# Doggy.net
KiCad netlist of a schematic drawn in Altium Designer
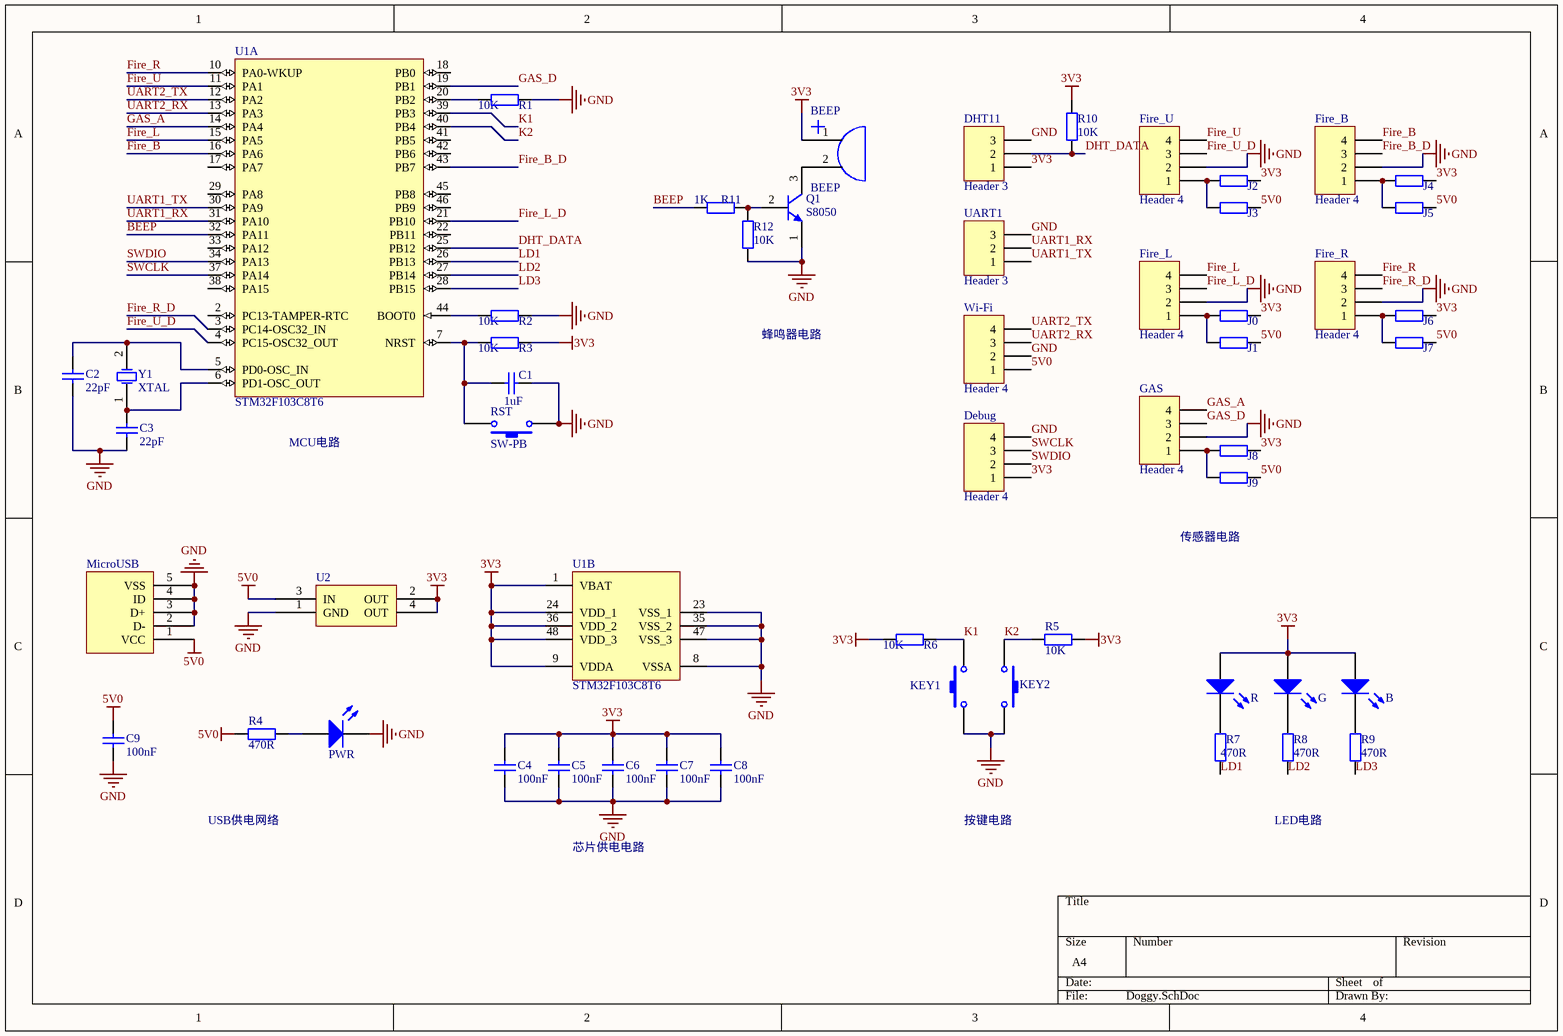
[diagram p0: Doggy.SchDoc]

(export (version "E")
  (design (tool "Eeschema 10.0.6"))
  (components
    (comp (ref "B")
      (value "LED0")
      (footprint "LED_0805")
      (description "发光二极管")
      (fields (field (name "PUBLISHER") "Altium Limited"))
      (libsource (lib "Fszhang") (part "LED0"))
    )
    (comp (ref "BEEP")
      (value "BEEP")
      (footprint "Beep")
      (description "蜂鸣器")
      (libsource (lib "Fszhang") (part "BEEP"))
    )
    (comp (ref "C1")
      (value "1uF")
      (footprint "C-RAD-0805")
      (description "无极性电容")
      (fields (field (name "Comment") "Cap") (field (name "PUBLISHER") "Altium Limited"))
      (libsource (lib "Fszhang") (part "Cap"))
    )
    (comp (ref "C2")
      (value "22pF")
      (footprint "C-RAD-0805")
      (description "无极性电容")
      (fields (field (name "Comment") "Cap") (field (name "PUBLISHER") "Altium Limited"))
      (libsource (lib "Fszhang") (part "Cap"))
    )
    (comp (ref "C3")
      (value "22pF")
      (footprint "C-RAD-0805")
      (description "无极性电容")
      (fields (field (name "Comment") "Cap") (field (name "PUBLISHER") "Altium Limited"))
      (libsource (lib "Fszhang") (part "Cap"))
    )
    (comp (ref "C4")
      (value "100nF")
      (footprint "C-RAD-0805")
      (description "无极性电容")
      (fields (field (name "Comment") "Cap") (field (name "PUBLISHER") "Altium Limited"))
      (libsource (lib "Fszhang") (part "Cap"))
    )
    (comp (ref "C5")
      (value "100nF")
      (footprint "C-RAD-0805")
      (description "无极性电容")
      (fields (field (name "Comment") "Cap") (field (name "PUBLISHER") "Altium Limited"))
      (libsource (lib "Fszhang") (part "Cap"))
    )
    (comp (ref "C6")
      (value "100nF")
      (footprint "C-RAD-0805")
      (description "无极性电容")
      (fields (field (name "Comment") "Cap") (field (name "PUBLISHER") "Altium Limited"))
      (libsource (lib "Fszhang") (part "Cap"))
    )
    (comp (ref "C7")
      (value "100nF")
      (footprint "C-RAD-0805")
      (description "无极性电容")
      (fields (field (name "Comment") "Cap") (field (name "PUBLISHER") "Altium Limited"))
      (libsource (lib "Fszhang") (part "Cap"))
    )
    (comp (ref "C8")
      (value "100nF")
      (footprint "C-RAD-0805")
      (description "无极性电容")
      (fields (field (name "Comment") "Cap") (field (name "PUBLISHER") "Altium Limited"))
      (libsource (lib "Fszhang") (part "Cap"))
    )
    (comp (ref "C9")
      (value "100nF")
      (footprint "C-RAD-0805")
      (description "无极性电容")
      (fields (field (name "Comment") "Cap") (field (name "PUBLISHER") "Altium Limited"))
      (libsource (lib "Fszhang") (part "Cap"))
    )
    (comp (ref "Debug")
      (value "Header 4")
      (footprint "HDR1X4")
      (description "Header, 4-Pin")
      (fields (field (name "PUBLISHER") "Altium Limited"))
      (libsource (lib "Miscellaneous Connectors") (part "Header 4"))
    )
    (comp (ref "DHT11")
      (value "Header 3")
      (footprint "HDR1X3")
      (description "Header, 3-Pin")
      (fields (field (name "PUBLISHER") "Altium Limited"))
      (libsource (lib "Miscellaneous Connectors") (part "Header 3"))
    )
    (comp (ref "Fire_B")
      (value "Header 4")
      (footprint "HDR1X4")
      (description "Header, 4-Pin")
      (fields (field (name "PUBLISHER") "Altium Limited"))
      (libsource (lib "Miscellaneous Connectors") (part "Header 4"))
    )
    (comp (ref "Fire_L")
      (value "Header 4")
      (footprint "HDR1X4")
      (description "Header, 4-Pin")
      (fields (field (name "PUBLISHER") "Altium Limited"))
      (libsource (lib "Miscellaneous Connectors") (part "Header 4"))
    )
    (comp (ref "Fire_R")
      (value "Header 4")
      (footprint "HDR1X4")
      (description "Header, 4-Pin")
      (fields (field (name "PUBLISHER") "Altium Limited"))
      (libsource (lib "Miscellaneous Connectors") (part "Header 4"))
    )
    (comp (ref "Fire_U")
      (value "Header 4")
      (footprint "HDR1X4")
      (description "Header, 4-Pin")
      (fields (field (name "PUBLISHER") "Altium Limited"))
      (libsource (lib "Miscellaneous Connectors") (part "Header 4"))
    )
    (comp (ref "G")
      (value "LED0")
      (footprint "LED_0805")
      (description "发光二极管")
      (fields (field (name "PUBLISHER") "Altium Limited"))
      (libsource (lib "Fszhang") (part "LED0"))
    )
    (comp (ref "GAS")
      (value "Header 4")
      (footprint "HDR1X4")
      (description "Header, 4-Pin")
      (fields (field (name "PUBLISHER") "Altium Limited"))
      (libsource (lib "Miscellaneous Connectors") (part "Header 4"))
    )
    (comp (ref "J0")
      (value "Res1")
      (footprint "0805-1")
      (description "贴片电阻")
      (fields (field (name "PUBLISHER") "Altium Limited"))
      (libsource (lib "Fszhang") (part "Res1"))
    )
    (comp (ref "J1")
      (value "Res1")
      (footprint "0805-1")
      (description "贴片电阻")
      (fields (field (name "PUBLISHER") "Altium Limited"))
      (libsource (lib "Fszhang") (part "Res1"))
    )
    (comp (ref "J2")
      (value "Res1")
      (footprint "0805-1")
      (description "贴片电阻")
      (fields (field (name "PUBLISHER") "Altium Limited"))
      (libsource (lib "Fszhang") (part "Res1"))
    )
    (comp (ref "J3")
      (value "Res1")
      (footprint "0805-1")
      (description "贴片电阻")
      (fields (field (name "PUBLISHER") "Altium Limited"))
      (libsource (lib "Fszhang") (part "Res1"))
    )
    (comp (ref "J4")
      (value "Res1")
      (footprint "0805-1")
      (description "贴片电阻")
      (fields (field (name "PUBLISHER") "Altium Limited"))
      (libsource (lib "Fszhang") (part "Res1"))
    )
    (comp (ref "J5")
      (value "Res1")
      (footprint "0805-1")
      (description "贴片电阻")
      (fields (field (name "PUBLISHER") "Altium Limited"))
      (libsource (lib "Fszhang") (part "Res1"))
    )
    (comp (ref "J6")
      (value "Res1")
      (footprint "0805-1")
      (description "贴片电阻")
      (fields (field (name "PUBLISHER") "Altium Limited"))
      (libsource (lib "Fszhang") (part "Res1"))
    )
    (comp (ref "J7")
      (value "Res1")
      (footprint "0805-1")
      (description "贴片电阻")
      (fields (field (name "PUBLISHER") "Altium Limited"))
      (libsource (lib "Fszhang") (part "Res1"))
    )
    (comp (ref "J8")
      (value "Res1")
      (footprint "0805-1")
      (description "贴片电阻")
      (fields (field (name "PUBLISHER") "Altium Limited"))
      (libsource (lib "Fszhang") (part "Res1"))
    )
    (comp (ref "J9")
      (value "Res1")
      (footprint "0805-1")
      (description "贴片电阻")
      (fields (field (name "PUBLISHER") "Altium Limited"))
      (libsource (lib "Fszhang") (part "Res1"))
    )
    (comp (ref "KEY1")
      (value "SW-PB")
      (footprint "SW_PB2_A1")
      (description "微动开关")
      (fields (field (name "PUBLISHER") "Altium Limited"))
      (libsource (lib "Fszhang") (part "SW-PB"))
    )
    (comp (ref "KEY2")
      (value "SW-PB")
      (footprint "SW_PB2_A1")
      (description "微动开关")
      (fields (field (name "PUBLISHER") "Altium Limited"))
      (libsource (lib "Fszhang") (part "SW-PB"))
    )
    (comp (ref "MicroUSB")
      (value "USB_M")
      (footprint "USB_MICRO")
      (description "MicroUSB接口")
      (libsource (lib "Fszhang") (part "USB_M"))
    )
    (comp (ref "PWR")
      (value "LED0")
      (footprint "LED_0805")
      (description "发光二极管")
      (fields (field (name "PUBLISHER") "Altium Limited"))
      (libsource (lib "Fszhang") (part "LED0"))
    )
    (comp (ref "Q1")
      (value "S8050")
      (footprint "TO-92A")
      (description "NPN三极管")
      (fields (field (name "PUBLISHER") "Altium Limited"))
      (libsource (lib "Fszhang") (part "S8050"))
    )
    (comp (ref "R")
      (value "LED0")
      (footprint "LED_0805")
      (description "发光二极管")
      (fields (field (name "PUBLISHER") "Altium Limited"))
      (libsource (lib "Fszhang") (part "LED0"))
    )
    (comp (ref "R1")
      (value "10K")
      (footprint "0805-1")
      (description "贴片电阻")
      (fields (field (name "Comment") "Res1") (field (name "PUBLISHER") "Altium Limited"))
      (libsource (lib "Fszhang") (part "Res1"))
    )
    (comp (ref "R2")
      (value "10K")
      (footprint "0805-1")
      (description "贴片电阻")
      (fields (field (name "Comment") "Res1") (field (name "PUBLISHER") "Altium Limited"))
      (libsource (lib "Fszhang") (part "Res1"))
    )
    (comp (ref "R3")
      (value "10K")
      (footprint "0805-1")
      (description "贴片电阻")
      (fields (field (name "Comment") "Res1") (field (name "PUBLISHER") "Altium Limited"))
      (libsource (lib "Fszhang") (part "Res1"))
    )
    (comp (ref "R4")
      (value "470R")
      (footprint "0805-1")
      (description "贴片电阻")
      (fields (field (name "Comment") "Res1") (field (name "PUBLISHER") "Altium Limited"))
      (libsource (lib "Fszhang") (part "Res1"))
    )
    (comp (ref "R5")
      (value "10K")
      (footprint "0805-1")
      (description "贴片电阻")
      (fields (field (name "Comment") "Res1") (field (name "PUBLISHER") "Altium Limited"))
      (libsource (lib "") (part "Res1_1"))
    )
    (comp (ref "R6")
      (value "10K")
      (footprint "0805-1")
      (description "贴片电阻")
      (fields (field (name "Comment") "Res1") (field (name "PUBLISHER") "Altium Limited"))
      (libsource (lib "Fszhang") (part "Res1"))
    )
    (comp (ref "R7")
      (value "470R")
      (footprint "0805-1")
      (description "贴片电阻")
      (fields (field (name "Comment") "Res1") (field (name "PUBLISHER") "Altium Limited"))
      (libsource (lib "") (part "Res1_2"))
    )
    (comp (ref "R8")
      (value "470R")
      (footprint "0805-1")
      (description "贴片电阻")
      (fields (field (name "Comment") "Res1") (field (name "PUBLISHER") "Altium Limited"))
      (libsource (lib "") (part "Res1_2"))
    )
    (comp (ref "R9")
      (value "470R")
      (footprint "0805-1")
      (description "贴片电阻")
      (fields (field (name "Comment") "Res1") (field (name "PUBLISHER") "Altium Limited"))
      (libsource (lib "") (part "Res1_2"))
    )
    (comp (ref "R10")
      (value "10K")
      (footprint "0805-1")
      (description "贴片电阻")
      (fields (field (name "Comment") "Res1") (field (name "PUBLISHER") "Altium Limited"))
      (libsource (lib "") (part "Res1_2"))
    )
    (comp (ref "R11")
      (value "1K")
      (footprint "0805-1")
      (description "贴片电阻")
      (fields (field (name "Comment") "Res1") (field (name "PUBLISHER") "Altium Limited"))
      (libsource (lib "Fszhang") (part "Res1"))
    )
    (comp (ref "R12")
      (value "10K")
      (footprint "0805-1")
      (description "贴片电阻")
      (fields (field (name "Comment") "Res1") (field (name "PUBLISHER") "Altium Limited"))
      (libsource (lib "") (part "Res1_2"))
    )
    (comp (ref "RST")
      (value "SW-PB")
      (footprint "SW_PB2_A1")
      (description "微动开关")
      (fields (field (name "PUBLISHER") "Altium Limited"))
      (libsource (lib "Fszhang") (part "SW-PB"))
    )
    (comp (ref "U1")
      (value "STM32F103C8T6")
      (footprint "STM-LQFP48_N")
      (libsource (lib "STMicroelectronics STM32 F1") (part "STM32F103C8T6"))
    )
    (comp (ref "U2")
      (value "AMS1117-3.3")
      (footprint "SOT-223")
      (description "3.3V稳压芯片")
      (libsource (lib "Fszhang") (part "ASM1117"))
    )
    (comp (ref "UART1")
      (value "Header 3")
      (footprint "HDR1X3")
      (description "Header, 3-Pin")
      (fields (field (name "PUBLISHER") "Altium Limited"))
      (libsource (lib "Miscellaneous Connectors") (part "Header 3"))
    )
    (comp (ref "Wi-Fi")
      (value "Header 4")
      (footprint "HDR1X4")
      (description "Header, 4-Pin")
      (fields (field (name "PUBLISHER") "Altium Limited"))
      (libsource (lib "Miscellaneous Connectors") (part "Header 4"))
    )
    (comp (ref "Y1")
      (value "XTAL")
      (footprint "X-HC49U")
      (description "Crystal Oscillator")
      (fields (field (name "PUBLISHER") "Altium Limited"))
      (libsource (lib "Miscellaneous Devices") (part "XTAL"))
    )
  )
  (nets
    (net (code "1") (name "/BEEP") (class "Default")
      (node (ref "R11") (pin "1") (pinfunction "1_1") (pintype "passive"))
      (node (ref "U1") (pin "32") (pinfunction "PA11_32") (pintype "bidirectional"))
    )
    (net (code "2") (name "/DHT_DATA") (class "Default")
      (node (ref "DHT11") (pin "2") (pinfunction "2_2") (pintype "passive"))
      (node (ref "R10") (pin "1") (pinfunction "1_1") (pintype "passive"))
      (node (ref "U1") (pin "25") (pinfunction "PB12_25") (pintype "bidirectional"))
    )
    (net (code "3") (name "/Fire_B") (class "Default")
      (node (ref "Fire_B") (pin "4") (pinfunction "4_4") (pintype "passive"))
      (node (ref "U1") (pin "16") (pinfunction "PA6_16") (pintype "bidirectional"))
    )
    (net (code "4") (name "/Fire_B_D") (class "Default")
      (node (ref "Fire_B") (pin "3") (pinfunction "3_3") (pintype "passive"))
      (node (ref "U1") (pin "43") (pinfunction "PB7_43") (pintype "bidirectional"))
    )
    (net (code "5") (name "/Fire_L") (class "Default")
      (node (ref "Fire_L") (pin "4") (pinfunction "4_4") (pintype "passive"))
      (node (ref "U1") (pin "15") (pinfunction "PA5_15") (pintype "bidirectional"))
    )
    (net (code "6") (name "/Fire_L_D") (class "Default")
      (node (ref "Fire_L") (pin "3") (pinfunction "3_3") (pintype "passive"))
      (node (ref "U1") (pin "21") (pinfunction "PB10_21") (pintype "bidirectional"))
    )
    (net (code "7") (name "/Fire_R") (class "Default")
      (node (ref "Fire_R") (pin "4") (pinfunction "4_4") (pintype "passive"))
      (node (ref "U1") (pin "10") (pinfunction "PA0-WKUP_10") (pintype "bidirectional"))
    )
    (net (code "8") (name "/Fire_R_D") (class "Default")
      (node (ref "Fire_R") (pin "3") (pinfunction "3_3") (pintype "passive"))
      (node (ref "U1") (pin "3") (pinfunction "PC14-OSC32_IN_3") (pintype "bidirectional"))
    )
    (net (code "9") (name "/Fire_U") (class "Default")
      (node (ref "Fire_U") (pin "4") (pinfunction "4_4") (pintype "passive"))
      (node (ref "U1") (pin "11") (pinfunction "PA1_11") (pintype "bidirectional"))
    )
    (net (code "10") (name "/Fire_U_D") (class "Default")
      (node (ref "Fire_U") (pin "3") (pinfunction "3_3") (pintype "passive"))
      (node (ref "U1") (pin "4") (pinfunction "PC15-OSC32_OUT_4") (pintype "bidirectional"))
    )
    (net (code "11") (name "/GAS_A") (class "Default")
      (node (ref "GAS") (pin "4") (pinfunction "4_4") (pintype "passive"))
      (node (ref "U1") (pin "14") (pinfunction "PA4_14") (pintype "bidirectional"))
    )
    (net (code "12") (name "/GAS_D") (class "Default")
      (node (ref "GAS") (pin "3") (pinfunction "3_3") (pintype "passive"))
      (node (ref "U1") (pin "19") (pinfunction "PB1_19") (pintype "bidirectional"))
    )
    (net (code "13") (name "/K1") (class "Default")
      (node (ref "KEY1") (pin "2") (pinfunction "2_2") (pintype "passive"))
      (node (ref "R6") (pin "2") (pinfunction "2_2") (pintype "passive"))
      (node (ref "U1") (pin "39") (pinfunction "PB3_39") (pintype "bidirectional"))
    )
    (net (code "14") (name "/K2") (class "Default")
      (node (ref "KEY2") (pin "1") (pinfunction "1_1") (pintype "passive"))
      (node (ref "R5") (pin "2") (pinfunction "2_2") (pintype "passive"))
      (node (ref "U1") (pin "40") (pinfunction "PB4_40") (pintype "bidirectional"))
    )
    (net (code "15") (name "/LD1") (class "Default")
      (node (ref "R7") (pin "1") (pinfunction "1_1") (pintype "passive"))
      (node (ref "U1") (pin "26") (pinfunction "PB13_26") (pintype "bidirectional"))
    )
    (net (code "16") (name "/LD2") (class "Default")
      (node (ref "R8") (pin "1") (pinfunction "1_1") (pintype "passive"))
      (node (ref "U1") (pin "27") (pinfunction "PB14_27") (pintype "bidirectional"))
    )
    (net (code "17") (name "/LD3") (class "Default")
      (node (ref "R9") (pin "1") (pinfunction "1_1") (pintype "passive"))
      (node (ref "U1") (pin "28") (pinfunction "PB15_28") (pintype "bidirectional"))
    )
    (net (code "18") (name "/SWCLK") (class "Default")
      (node (ref "Debug") (pin "3") (pinfunction "3_3") (pintype "passive"))
      (node (ref "U1") (pin "37") (pinfunction "PA14_37") (pintype "bidirectional"))
    )
    (net (code "19") (name "/SWDIO") (class "Default")
      (node (ref "Debug") (pin "2") (pinfunction "2_2") (pintype "passive"))
      (node (ref "U1") (pin "34") (pinfunction "PA13_34") (pintype "bidirectional"))
    )
    (net (code "20") (name "/UART1_RX") (class "Default")
      (node (ref "U1") (pin "31") (pinfunction "PA10_31") (pintype "bidirectional"))
      (node (ref "UART1") (pin "2") (pinfunction "2_2") (pintype "passive"))
    )
    (net (code "21") (name "/UART1_TX") (class "Default")
      (node (ref "U1") (pin "30") (pinfunction "PA9_30") (pintype "bidirectional"))
      (node (ref "UART1") (pin "1") (pinfunction "1_1") (pintype "passive"))
    )
    (net (code "22") (name "/UART2_RX") (class "Default")
      (node (ref "U1") (pin "13") (pinfunction "PA3_13") (pintype "bidirectional"))
      (node (ref "Wi-Fi") (pin "3") (pinfunction "3_3") (pintype "passive"))
    )
    (net (code "23") (name "/UART2_TX") (class "Default")
      (node (ref "U1") (pin "12") (pinfunction "PA2_12") (pintype "bidirectional"))
      (node (ref "Wi-Fi") (pin "4") (pinfunction "4_4") (pintype "passive"))
    )
    (net (code "24") (name "3V3") (class "Default")
      (node (ref "B") (pin "1") (pinfunction "A_1") (pintype "passive"))
      (node (ref "BEEP") (pin "1") (pinfunction "0_1") (pintype "passive"))
      (node (ref "C4") (pin "2") (pinfunction "2_2") (pintype "passive"))
      (node (ref "C5") (pin "2") (pinfunction "2_2") (pintype "passive"))
      (node (ref "C6") (pin "2") (pinfunction "2_2") (pintype "passive"))
      (node (ref "C7") (pin "2") (pinfunction "2_2") (pintype "passive"))
      (node (ref "C8") (pin "2") (pinfunction "2_2") (pintype "passive"))
      (node (ref "DHT11") (pin "1") (pinfunction "1_1") (pintype "passive"))
      (node (ref "Debug") (pin "1") (pinfunction "1_1") (pintype "passive"))
      (node (ref "G") (pin "1") (pinfunction "A_1") (pintype "passive"))
      (node (ref "J0") (pin "2") (pinfunction "2_2") (pintype "passive"))
      (node (ref "J2") (pin "2") (pinfunction "2_2") (pintype "passive"))
      (node (ref "J4") (pin "2") (pinfunction "2_2") (pintype "passive"))
      (node (ref "J6") (pin "2") (pinfunction "2_2") (pintype "passive"))
      (node (ref "J8") (pin "2") (pinfunction "2_2") (pintype "passive"))
      (node (ref "R") (pin "1") (pinfunction "A_1") (pintype "passive"))
      (node (ref "R10") (pin "2") (pinfunction "2_2") (pintype "passive"))
      (node (ref "R3") (pin "2") (pinfunction "2_2") (pintype "passive"))
      (node (ref "R5") (pin "1") (pinfunction "1_1") (pintype "passive"))
      (node (ref "R6") (pin "1") (pinfunction "1_1") (pintype "passive"))
      (node (ref "U1") (pin "1") (pinfunction "VBAT_1") (pintype "power_in"))
      (node (ref "U1") (pin "24") (pinfunction "VDD_1_24") (pintype "power_in"))
      (node (ref "U1") (pin "36") (pinfunction "VDD_2_36") (pintype "power_in"))
      (node (ref "U1") (pin "48") (pinfunction "VDD_3_48") (pintype "power_in"))
      (node (ref "U1") (pin "9") (pinfunction "VDDA_9") (pintype "power_in"))
      (node (ref "U2") (pin "2") (pinfunction "OUT_2") (pintype "passive"))
      (node (ref "U2") (pin "4") (pinfunction "OUT_4") (pintype "passive"))
    )
    (net (code "25") (name "5V0") (class "Default")
      (node (ref "C9") (pin "2") (pinfunction "2_2") (pintype "passive"))
      (node (ref "J1") (pin "2") (pinfunction "2_2") (pintype "passive"))
      (node (ref "J3") (pin "2") (pinfunction "2_2") (pintype "passive"))
      (node (ref "J5") (pin "2") (pinfunction "2_2") (pintype "passive"))
      (node (ref "J7") (pin "2") (pinfunction "2_2") (pintype "passive"))
      (node (ref "J9") (pin "2") (pinfunction "2_2") (pintype "passive"))
      (node (ref "MicroUSB") (pin "1") (pinfunction "VCC_1") (pintype "passive"))
      (node (ref "R4") (pin "1") (pinfunction "1_1") (pintype "passive"))
      (node (ref "U2") (pin "3") (pinfunction "IN_3") (pintype "passive"))
      (node (ref "Wi-Fi") (pin "1") (pinfunction "1_1") (pintype "passive"))
    )
    (net (code "26") (name "GND") (class "Default")
      (node (ref "C1") (pin "1") (pinfunction "1_1") (pintype "passive"))
      (node (ref "C2") (pin "1") (pinfunction "1_1") (pintype "passive"))
      (node (ref "C3") (pin "1") (pinfunction "1_1") (pintype "passive"))
      (node (ref "C4") (pin "1") (pinfunction "1_1") (pintype "passive"))
      (node (ref "C5") (pin "1") (pinfunction "1_1") (pintype "passive"))
      (node (ref "C6") (pin "1") (pinfunction "1_1") (pintype "passive"))
      (node (ref "C7") (pin "1") (pinfunction "1_1") (pintype "passive"))
      (node (ref "C8") (pin "1") (pinfunction "1_1") (pintype "passive"))
      (node (ref "C9") (pin "1") (pinfunction "1_1") (pintype "passive"))
      (node (ref "DHT11") (pin "3") (pinfunction "3_3") (pintype "passive"))
      (node (ref "Debug") (pin "4") (pinfunction "4_4") (pintype "passive"))
      (node (ref "Fire_B") (pin "2") (pinfunction "2_2") (pintype "passive"))
      (node (ref "Fire_L") (pin "2") (pinfunction "2_2") (pintype "passive"))
      (node (ref "Fire_R") (pin "2") (pinfunction "2_2") (pintype "passive"))
      (node (ref "Fire_U") (pin "2") (pinfunction "2_2") (pintype "passive"))
      (node (ref "GAS") (pin "2") (pinfunction "2_2") (pintype "passive"))
      (node (ref "KEY1") (pin "1") (pinfunction "1_1") (pintype "passive"))
      (node (ref "KEY2") (pin "2") (pinfunction "2_2") (pintype "passive"))
      (node (ref "MicroUSB") (pin "2") (pinfunction "D-_2") (pintype "passive"))
      (node (ref "MicroUSB") (pin "3") (pinfunction "D+_3") (pintype "passive"))
      (node (ref "MicroUSB") (pin "4") (pinfunction "ID_4") (pintype "passive"))
      (node (ref "MicroUSB") (pin "5") (pinfunction "VSS_5") (pintype "passive"))
      (node (ref "PWR") (pin "2") (pinfunction "K_2") (pintype "passive"))
      (node (ref "Q1") (pin "1") (pinfunction "E_1") (pintype "passive"))
      (node (ref "R1") (pin "2") (pinfunction "2_2") (pintype "passive"))
      (node (ref "R12") (pin "1") (pinfunction "1_1") (pintype "passive"))
      (node (ref "R2") (pin "2") (pinfunction "2_2") (pintype "passive"))
      (node (ref "RST") (pin "1") (pinfunction "1_1") (pintype "passive"))
      (node (ref "U1") (pin "23") (pinfunction "VSS_1_23") (pintype "power_in"))
      (node (ref "U1") (pin "35") (pinfunction "VSS_2_35") (pintype "power_in"))
      (node (ref "U1") (pin "47") (pinfunction "VSS_3_47") (pintype "power_in"))
      (node (ref "U1") (pin "8") (pinfunction "VSSA_8") (pintype "power_in"))
      (node (ref "U2") (pin "1") (pinfunction "GND_1") (pintype "passive"))
      (node (ref "UART1") (pin "3") (pinfunction "3_3") (pintype "passive"))
      (node (ref "Wi-Fi") (pin "2") (pinfunction "2_2") (pintype "passive"))
    )
    (net (code "27") (name "Net-(B-K)") (class "Default")
      (node (ref "B") (pin "2") (pinfunction "K_2") (pintype "passive"))
      (node (ref "R9") (pin "2") (pinfunction "2_2") (pintype "passive"))
    )
    (net (code "28") (name "Net-(BEEP-1)") (class "Default")
      (node (ref "BEEP") (pin "2") (pinfunction "1_2") (pintype "passive"))
      (node (ref "Q1") (pin "3") (pinfunction "C_3") (pintype "passive"))
    )
    (net (code "29") (name "Net-(Fire_B-Pad1)") (class "Default")
      (node (ref "Fire_B") (pin "1") (pinfunction "1_1") (pintype "passive"))
      (node (ref "J4") (pin "1") (pinfunction "1_1") (pintype "passive"))
      (node (ref "J5") (pin "1") (pinfunction "1_1") (pintype "passive"))
    )
    (net (code "30") (name "Net-(Fire_L-Pad1)") (class "Default")
      (node (ref "Fire_L") (pin "1") (pinfunction "1_1") (pintype "passive"))
      (node (ref "J0") (pin "1") (pinfunction "1_1") (pintype "passive"))
      (node (ref "J1") (pin "1") (pinfunction "1_1") (pintype "passive"))
    )
    (net (code "31") (name "Net-(Fire_R-Pad1)") (class "Default")
      (node (ref "Fire_R") (pin "1") (pinfunction "1_1") (pintype "passive"))
      (node (ref "J6") (pin "1") (pinfunction "1_1") (pintype "passive"))
      (node (ref "J7") (pin "1") (pinfunction "1_1") (pintype "passive"))
    )
    (net (code "32") (name "Net-(Fire_U-Pad1)") (class "Default")
      (node (ref "Fire_U") (pin "1") (pinfunction "1_1") (pintype "passive"))
      (node (ref "J2") (pin "1") (pinfunction "1_1") (pintype "passive"))
      (node (ref "J3") (pin "1") (pinfunction "1_1") (pintype "passive"))
    )
    (net (code "33") (name "Net-(G-K)") (class "Default")
      (node (ref "G") (pin "2") (pinfunction "K_2") (pintype "passive"))
      (node (ref "R8") (pin "2") (pinfunction "2_2") (pintype "passive"))
    )
    (net (code "34") (name "Net-(GAS-Pad1)") (class "Default")
      (node (ref "GAS") (pin "1") (pinfunction "1_1") (pintype "passive"))
      (node (ref "J8") (pin "1") (pinfunction "1_1") (pintype "passive"))
      (node (ref "J9") (pin "1") (pinfunction "1_1") (pintype "passive"))
    )
    (net (code "35") (name "Net-(PWR-A)") (class "Default")
      (node (ref "PWR") (pin "1") (pinfunction "A_1") (pintype "passive"))
      (node (ref "R4") (pin "2") (pinfunction "2_2") (pintype "passive"))
    )
    (net (code "36") (name "Net-(Q1-B)") (class "Default")
      (node (ref "Q1") (pin "2") (pinfunction "B_2") (pintype "passive"))
      (node (ref "R11") (pin "2") (pinfunction "2_2") (pintype "passive"))
      (node (ref "R12") (pin "2") (pinfunction "2_2") (pintype "passive"))
    )
    (net (code "37") (name "Net-(R-K)") (class "Default")
      (node (ref "R") (pin "2") (pinfunction "K_2") (pintype "passive"))
      (node (ref "R7") (pin "2") (pinfunction "2_2") (pintype "passive"))
    )
    (net (code "38") (name "Net-(U1A-BOOT0)") (class "Default")
      (node (ref "R2") (pin "1") (pinfunction "1_1") (pintype "passive"))
      (node (ref "U1") (pin "44") (pinfunction "BOOT0_44") (pintype "input"))
    )
    (net (code "39") (name "Net-(U1A-NRST)") (class "Default")
      (node (ref "C1") (pin "2") (pinfunction "2_2") (pintype "passive"))
      (node (ref "R3") (pin "1") (pinfunction "1_1") (pintype "passive"))
      (node (ref "RST") (pin "2") (pinfunction "2_2") (pintype "passive"))
      (node (ref "U1") (pin "7") (pinfunction "NRST_7") (pintype "bidirectional"))
    )
    (net (code "40") (name "Net-(U1A-PB2)") (class "Default")
      (node (ref "R1") (pin "1") (pinfunction "1_1") (pintype "passive"))
      (node (ref "U1") (pin "20") (pinfunction "PB2_20") (pintype "bidirectional"))
    )
    (net (code "41") (name "Net-(U1A-PD0-OSC_IN)") (class "Default")
      (node (ref "C2") (pin "2") (pinfunction "2_2") (pintype "passive"))
      (node (ref "U1") (pin "5") (pinfunction "PD0-OSC_IN_5") (pintype "bidirectional"))
      (node (ref "Y1") (pin "2") (pinfunction "OSC2_2") (pintype "passive"))
    )
    (net (code "42") (name "Net-(U1A-PD1-OSC_OUT)") (class "Default")
      (node (ref "C3") (pin "2") (pinfunction "2_2") (pintype "passive"))
      (node (ref "U1") (pin "6") (pinfunction "PD1-OSC_OUT_6") (pintype "bidirectional"))
      (node (ref "Y1") (pin "1") (pinfunction "OSC1_1") (pintype "passive"))
    )
    (net (code "43") (name "unconnected-(U1A-PA7-Pad17)") (class "Default")
      (node (ref "U1") (pin "17") (pinfunction "PA7_17") (pintype "bidirectional"))
    )
    (net (code "44") (name "unconnected-(U1A-PA8-Pad29)") (class "Default")
      (node (ref "U1") (pin "29") (pinfunction "PA8_29") (pintype "bidirectional"))
    )
    (net (code "45") (name "unconnected-(U1A-PA12-Pad33)") (class "Default")
      (node (ref "U1") (pin "33") (pinfunction "PA12_33") (pintype "bidirectional"))
    )
    (net (code "46") (name "unconnected-(U1A-PA15-Pad38)") (class "Default")
      (node (ref "U1") (pin "38") (pinfunction "PA15_38") (pintype "bidirectional"))
    )
    (net (code "47") (name "unconnected-(U1A-PB0-Pad18)") (class "Default")
      (node (ref "U1") (pin "18") (pinfunction "PB0_18") (pintype "bidirectional"))
    )
    (net (code "48") (name "unconnected-(U1A-PB5-Pad41)") (class "Default")
      (node (ref "U1") (pin "41") (pinfunction "PB5_41") (pintype "bidirectional"))
    )
    (net (code "49") (name "unconnected-(U1A-PB6-Pad42)") (class "Default")
      (node (ref "U1") (pin "42") (pinfunction "PB6_42") (pintype "bidirectional"))
    )
    (net (code "50") (name "unconnected-(U1A-PB8-Pad45)") (class "Default")
      (node (ref "U1") (pin "45") (pinfunction "PB8_45") (pintype "bidirectional"))
    )
    (net (code "51") (name "unconnected-(U1A-PB9-Pad46)") (class "Default")
      (node (ref "U1") (pin "46") (pinfunction "PB9_46") (pintype "bidirectional"))
    )
    (net (code "52") (name "unconnected-(U1A-PB11-Pad22)") (class "Default")
      (node (ref "U1") (pin "22") (pinfunction "PB11_22") (pintype "bidirectional"))
    )
    (net (code "53") (name "unconnected-(U1A-PC13-TAMPER-RTC-Pad2)") (class "Default")
      (node (ref "U1") (pin "2") (pinfunction "PC13-TAMPER-RTC_2") (pintype "bidirectional"))
    )
  )
)
